# Fri3D_2018_LEDS_00.net
KiCad netlist of a schematic drawn in Altium Designer
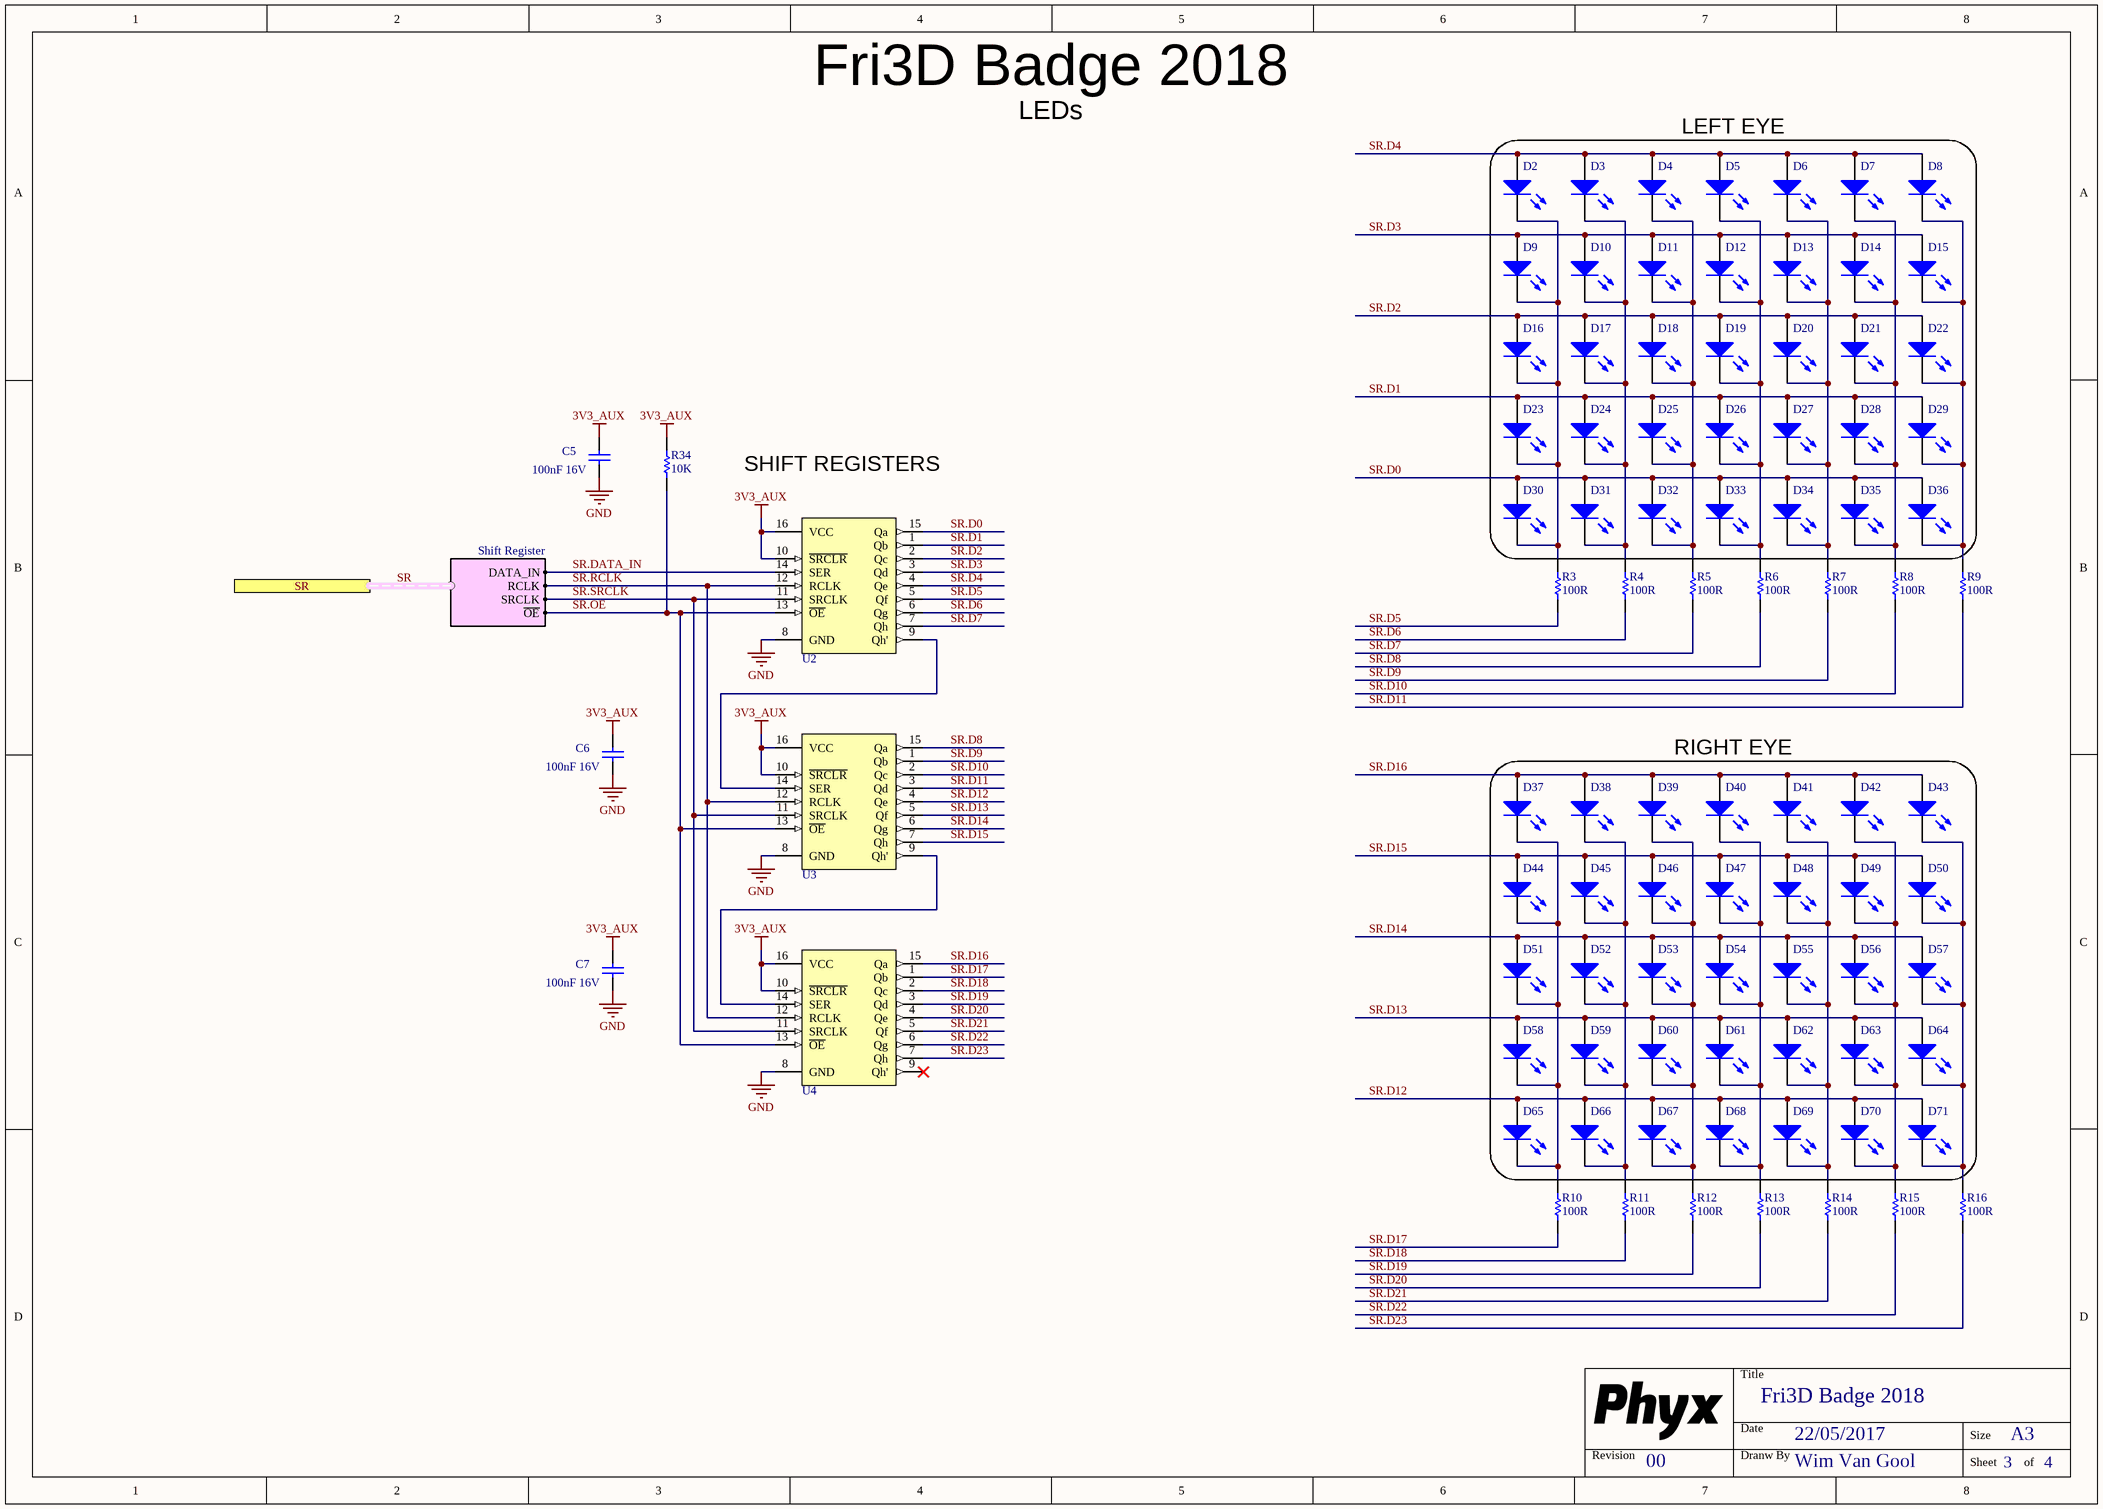
[diagram p0: Fri3D_2018_LEDS_00.SchDoc]

(export (version "E")
  (design (tool "Eeschema 10.0.6"))
  (components
    (comp (ref "C5")
      (value "100nF 16V")
      (footprint "C0603_N")
      (description "Capacitor Ceramic")
      (libsource (lib "Phyx_Components") (part "CAP_CERAMIC"))
    )
    (comp (ref "C6")
      (value "100nF 16V")
      (footprint "C0603_N")
      (description "Capacitor Ceramic")
      (libsource (lib "Phyx_Components") (part "CAP_CERAMIC"))
    )
    (comp (ref "C7")
      (value "100nF 16V")
      (footprint "C0603_N")
      (description "Capacitor Ceramic")
      (libsource (lib "Phyx_Components") (part "CAP_CERAMIC"))
    )
    (comp (ref "D2")
      (value "Default 0805 Blue LED")
      (footprint "LED_0805_BL")
      (description "=Description")
      (libsource (lib "Phyx_Components") (part "LED_BLUE"))
    )
    (comp (ref "D3")
      (value "Default 0805 Blue LED")
      (footprint "LED_0805_BL")
      (description "=Description")
      (libsource (lib "Phyx_Components") (part "LED_BLUE"))
    )
    (comp (ref "D4")
      (value "Default 0805 Blue LED")
      (footprint "LED_0805_BL")
      (description "=Description")
      (libsource (lib "Phyx_Components") (part "LED_BLUE"))
    )
    (comp (ref "D5")
      (value "Default 0805 Blue LED")
      (footprint "LED_0805_BL")
      (description "=Description")
      (libsource (lib "Phyx_Components") (part "LED_BLUE"))
    )
    (comp (ref "D6")
      (value "Default 0805 Blue LED")
      (footprint "LED_0805_BL")
      (description "=Description")
      (libsource (lib "Phyx_Components") (part "LED_BLUE"))
    )
    (comp (ref "D7")
      (value "Default 0805 Blue LED")
      (footprint "LED_0805_BL")
      (description "=Description")
      (libsource (lib "Phyx_Components") (part "LED_BLUE"))
    )
    (comp (ref "D8")
      (value "Default 0805 Blue LED")
      (footprint "LED_0805_BL")
      (description "=Description")
      (libsource (lib "Phyx_Components") (part "LED_BLUE"))
    )
    (comp (ref "D9")
      (value "Default 0805 Blue LED")
      (footprint "LED_0805_BL")
      (description "=Description")
      (libsource (lib "Phyx_Components") (part "LED_BLUE"))
    )
    (comp (ref "D10")
      (value "Default 0805 Blue LED")
      (footprint "LED_0805_BL")
      (description "=Description")
      (libsource (lib "Phyx_Components") (part "LED_BLUE"))
    )
    (comp (ref "D11")
      (value "Default 0805 Blue LED")
      (footprint "LED_0805_BL")
      (description "=Description")
      (libsource (lib "Phyx_Components") (part "LED_BLUE"))
    )
    (comp (ref "D12")
      (value "Default 0805 Blue LED")
      (footprint "LED_0805_BL")
      (description "=Description")
      (libsource (lib "Phyx_Components") (part "LED_BLUE"))
    )
    (comp (ref "D13")
      (value "Default 0805 Blue LED")
      (footprint "LED_0805_BL")
      (description "=Description")
      (libsource (lib "Phyx_Components") (part "LED_BLUE"))
    )
    (comp (ref "D14")
      (value "Default 0805 Blue LED")
      (footprint "LED_0805_BL")
      (description "=Description")
      (libsource (lib "Phyx_Components") (part "LED_BLUE"))
    )
    (comp (ref "D15")
      (value "Default 0805 Blue LED")
      (footprint "LED_0805_BL")
      (description "=Description")
      (libsource (lib "Phyx_Components") (part "LED_BLUE"))
    )
    (comp (ref "D16")
      (value "Default 0805 Blue LED")
      (footprint "LED_0805_BL")
      (description "=Description")
      (libsource (lib "Phyx_Components") (part "LED_BLUE"))
    )
    (comp (ref "D17")
      (value "Default 0805 Blue LED")
      (footprint "LED_0805_BL")
      (description "=Description")
      (libsource (lib "Phyx_Components") (part "LED_BLUE"))
    )
    (comp (ref "D18")
      (value "Default 0805 Blue LED")
      (footprint "LED_0805_BL")
      (description "=Description")
      (libsource (lib "Phyx_Components") (part "LED_BLUE"))
    )
    (comp (ref "D19")
      (value "Default 0805 Blue LED")
      (footprint "LED_0805_BL")
      (description "=Description")
      (libsource (lib "Phyx_Components") (part "LED_BLUE"))
    )
    (comp (ref "D20")
      (value "Default 0805 Blue LED")
      (footprint "LED_0805_BL")
      (description "=Description")
      (libsource (lib "Phyx_Components") (part "LED_BLUE"))
    )
    (comp (ref "D21")
      (value "Default 0805 Blue LED")
      (footprint "LED_0805_BL")
      (description "=Description")
      (libsource (lib "Phyx_Components") (part "LED_BLUE"))
    )
    (comp (ref "D22")
      (value "Default 0805 Blue LED")
      (footprint "LED_0805_BL")
      (description "=Description")
      (libsource (lib "Phyx_Components") (part "LED_BLUE"))
    )
    (comp (ref "D23")
      (value "Default 0805 Blue LED")
      (footprint "LED_0805_BL")
      (description "=Description")
      (libsource (lib "Phyx_Components") (part "LED_BLUE"))
    )
    (comp (ref "D24")
      (value "Default 0805 Blue LED")
      (footprint "LED_0805_BL")
      (description "=Description")
      (libsource (lib "Phyx_Components") (part "LED_BLUE"))
    )
    (comp (ref "D25")
      (value "Default 0805 Blue LED")
      (footprint "LED_0805_BL")
      (description "=Description")
      (libsource (lib "Phyx_Components") (part "LED_BLUE"))
    )
    (comp (ref "D26")
      (value "Default 0805 Blue LED")
      (footprint "LED_0805_BL")
      (description "=Description")
      (libsource (lib "Phyx_Components") (part "LED_BLUE"))
    )
    (comp (ref "D27")
      (value "Default 0805 Blue LED")
      (footprint "LED_0805_BL")
      (description "=Description")
      (libsource (lib "Phyx_Components") (part "LED_BLUE"))
    )
    (comp (ref "D28")
      (value "Default 0805 Blue LED")
      (footprint "LED_0805_BL")
      (description "=Description")
      (libsource (lib "Phyx_Components") (part "LED_BLUE"))
    )
    (comp (ref "D29")
      (value "Default 0805 Blue LED")
      (footprint "LED_0805_BL")
      (description "=Description")
      (libsource (lib "Phyx_Components") (part "LED_BLUE"))
    )
    (comp (ref "D30")
      (value "Default 0805 Blue LED")
      (footprint "LED_0805_BL")
      (description "=Description")
      (libsource (lib "Phyx_Components") (part "LED_BLUE"))
    )
    (comp (ref "D31")
      (value "Default 0805 Blue LED")
      (footprint "LED_0805_BL")
      (description "=Description")
      (libsource (lib "Phyx_Components") (part "LED_BLUE"))
    )
    (comp (ref "D32")
      (value "Default 0805 Blue LED")
      (footprint "LED_0805_BL")
      (description "=Description")
      (libsource (lib "Phyx_Components") (part "LED_BLUE"))
    )
    (comp (ref "D33")
      (value "Default 0805 Blue LED")
      (footprint "LED_0805_BL")
      (description "=Description")
      (libsource (lib "Phyx_Components") (part "LED_BLUE"))
    )
    (comp (ref "D34")
      (value "Default 0805 Blue LED")
      (footprint "LED_0805_BL")
      (description "=Description")
      (libsource (lib "Phyx_Components") (part "LED_BLUE"))
    )
    (comp (ref "D35")
      (value "Default 0805 Blue LED")
      (footprint "LED_0805_BL")
      (description "=Description")
      (libsource (lib "Phyx_Components") (part "LED_BLUE"))
    )
    (comp (ref "D36")
      (value "Default 0805 Blue LED")
      (footprint "LED_0805_BL")
      (description "=Description")
      (libsource (lib "Phyx_Components") (part "LED_BLUE"))
    )
    (comp (ref "D37")
      (value "Default 0805 Blue LED")
      (footprint "LED_0805_BL")
      (description "=Description")
      (libsource (lib "Phyx_Components") (part "LED_BLUE"))
    )
    (comp (ref "D38")
      (value "Default 0805 Blue LED")
      (footprint "LED_0805_BL")
      (description "=Description")
      (libsource (lib "Phyx_Components") (part "LED_BLUE"))
    )
    (comp (ref "D39")
      (value "Default 0805 Blue LED")
      (footprint "LED_0805_BL")
      (description "=Description")
      (libsource (lib "Phyx_Components") (part "LED_BLUE"))
    )
    (comp (ref "D40")
      (value "Default 0805 Blue LED")
      (footprint "LED_0805_BL")
      (description "=Description")
      (libsource (lib "Phyx_Components") (part "LED_BLUE"))
    )
    (comp (ref "D41")
      (value "Default 0805 Blue LED")
      (footprint "LED_0805_BL")
      (description "=Description")
      (libsource (lib "Phyx_Components") (part "LED_BLUE"))
    )
    (comp (ref "D42")
      (value "Default 0805 Blue LED")
      (footprint "LED_0805_BL")
      (description "=Description")
      (libsource (lib "Phyx_Components") (part "LED_BLUE"))
    )
    (comp (ref "D43")
      (value "Default 0805 Blue LED")
      (footprint "LED_0805_BL")
      (description "=Description")
      (libsource (lib "Phyx_Components") (part "LED_BLUE"))
    )
    (comp (ref "D44")
      (value "Default 0805 Blue LED")
      (footprint "LED_0805_BL")
      (description "=Description")
      (libsource (lib "Phyx_Components") (part "LED_BLUE"))
    )
    (comp (ref "D45")
      (value "Default 0805 Blue LED")
      (footprint "LED_0805_BL")
      (description "=Description")
      (libsource (lib "Phyx_Components") (part "LED_BLUE"))
    )
    (comp (ref "D46")
      (value "Default 0805 Blue LED")
      (footprint "LED_0805_BL")
      (description "=Description")
      (libsource (lib "Phyx_Components") (part "LED_BLUE"))
    )
    (comp (ref "D47")
      (value "Default 0805 Blue LED")
      (footprint "LED_0805_BL")
      (description "=Description")
      (libsource (lib "Phyx_Components") (part "LED_BLUE"))
    )
    (comp (ref "D48")
      (value "Default 0805 Blue LED")
      (footprint "LED_0805_BL")
      (description "=Description")
      (libsource (lib "Phyx_Components") (part "LED_BLUE"))
    )
    (comp (ref "D49")
      (value "Default 0805 Blue LED")
      (footprint "LED_0805_BL")
      (description "=Description")
      (libsource (lib "Phyx_Components") (part "LED_BLUE"))
    )
    (comp (ref "D50")
      (value "Default 0805 Blue LED")
      (footprint "LED_0805_BL")
      (description "=Description")
      (libsource (lib "Phyx_Components") (part "LED_BLUE"))
    )
    (comp (ref "D51")
      (value "Default 0805 Blue LED")
      (footprint "LED_0805_BL")
      (description "=Description")
      (libsource (lib "Phyx_Components") (part "LED_BLUE"))
    )
    (comp (ref "D52")
      (value "Default 0805 Blue LED")
      (footprint "LED_0805_BL")
      (description "=Description")
      (libsource (lib "Phyx_Components") (part "LED_BLUE"))
    )
    (comp (ref "D53")
      (value "Default 0805 Blue LED")
      (footprint "LED_0805_BL")
      (description "=Description")
      (libsource (lib "Phyx_Components") (part "LED_BLUE"))
    )
    (comp (ref "D54")
      (value "Default 0805 Blue LED")
      (footprint "LED_0805_BL")
      (description "=Description")
      (libsource (lib "Phyx_Components") (part "LED_BLUE"))
    )
    (comp (ref "D55")
      (value "Default 0805 Blue LED")
      (footprint "LED_0805_BL")
      (description "=Description")
      (libsource (lib "Phyx_Components") (part "LED_BLUE"))
    )
    (comp (ref "D56")
      (value "Default 0805 Blue LED")
      (footprint "LED_0805_BL")
      (description "=Description")
      (libsource (lib "Phyx_Components") (part "LED_BLUE"))
    )
    (comp (ref "D57")
      (value "Default 0805 Blue LED")
      (footprint "LED_0805_BL")
      (description "=Description")
      (libsource (lib "Phyx_Components") (part "LED_BLUE"))
    )
    (comp (ref "D58")
      (value "Default 0805 Blue LED")
      (footprint "LED_0805_BL")
      (description "=Description")
      (libsource (lib "Phyx_Components") (part "LED_BLUE"))
    )
    (comp (ref "D59")
      (value "Default 0805 Blue LED")
      (footprint "LED_0805_BL")
      (description "=Description")
      (libsource (lib "Phyx_Components") (part "LED_BLUE"))
    )
    (comp (ref "D60")
      (value "Default 0805 Blue LED")
      (footprint "LED_0805_BL")
      (description "=Description")
      (libsource (lib "Phyx_Components") (part "LED_BLUE"))
    )
    (comp (ref "D61")
      (value "Default 0805 Blue LED")
      (footprint "LED_0805_BL")
      (description "=Description")
      (libsource (lib "Phyx_Components") (part "LED_BLUE"))
    )
    (comp (ref "D62")
      (value "Default 0805 Blue LED")
      (footprint "LED_0805_BL")
      (description "=Description")
      (libsource (lib "Phyx_Components") (part "LED_BLUE"))
    )
    (comp (ref "D63")
      (value "Default 0805 Blue LED")
      (footprint "LED_0805_BL")
      (description "=Description")
      (libsource (lib "Phyx_Components") (part "LED_BLUE"))
    )
    (comp (ref "D64")
      (value "Default 0805 Blue LED")
      (footprint "LED_0805_BL")
      (description "=Description")
      (libsource (lib "Phyx_Components") (part "LED_BLUE"))
    )
    (comp (ref "D65")
      (value "Default 0805 Blue LED")
      (footprint "LED_0805_BL")
      (description "=Description")
      (libsource (lib "Phyx_Components") (part "LED_BLUE"))
    )
    (comp (ref "D66")
      (value "Default 0805 Blue LED")
      (footprint "LED_0805_BL")
      (description "=Description")
      (libsource (lib "Phyx_Components") (part "LED_BLUE"))
    )
    (comp (ref "D67")
      (value "Default 0805 Blue LED")
      (footprint "LED_0805_BL")
      (description "=Description")
      (libsource (lib "Phyx_Components") (part "LED_BLUE"))
    )
    (comp (ref "D68")
      (value "Default 0805 Blue LED")
      (footprint "LED_0805_BL")
      (description "=Description")
      (libsource (lib "Phyx_Components") (part "LED_BLUE"))
    )
    (comp (ref "D69")
      (value "Default 0805 Blue LED")
      (footprint "LED_0805_BL")
      (description "=Description")
      (libsource (lib "Phyx_Components") (part "LED_BLUE"))
    )
    (comp (ref "D70")
      (value "Default 0805 Blue LED")
      (footprint "LED_0805_BL")
      (description "=Description")
      (libsource (lib "Phyx_Components") (part "LED_BLUE"))
    )
    (comp (ref "D71")
      (value "Default 0805 Blue LED")
      (footprint "LED_0805_BL")
      (description "=Description")
      (libsource (lib "Phyx_Components") (part "LED_BLUE"))
    )
    (comp (ref "R3")
      (value "100R")
      (footprint "R0603_N")
      (fields (field (name "Comment") "RESISTOR"))
      (libsource (lib "Phyx_Components") (part "RESISTOR"))
    )
    (comp (ref "R4")
      (value "100R")
      (footprint "R0603_N")
      (fields (field (name "Comment") "RESISTOR"))
      (libsource (lib "Phyx_Components") (part "RESISTOR"))
    )
    (comp (ref "R5")
      (value "100R")
      (footprint "R0603_N")
      (fields (field (name "Comment") "RESISTOR"))
      (libsource (lib "Phyx_Components") (part "RESISTOR"))
    )
    (comp (ref "R6")
      (value "100R")
      (footprint "R0603_N")
      (fields (field (name "Comment") "RESISTOR"))
      (libsource (lib "Phyx_Components") (part "RESISTOR"))
    )
    (comp (ref "R7")
      (value "100R")
      (footprint "R0603_N")
      (fields (field (name "Comment") "RESISTOR"))
      (libsource (lib "Phyx_Components") (part "RESISTOR"))
    )
    (comp (ref "R8")
      (value "100R")
      (footprint "R0603_N")
      (fields (field (name "Comment") "RESISTOR"))
      (libsource (lib "Phyx_Components") (part "RESISTOR"))
    )
    (comp (ref "R9")
      (value "100R")
      (footprint "R0603_N")
      (fields (field (name "Comment") "RESISTOR"))
      (libsource (lib "Phyx_Components") (part "RESISTOR"))
    )
    (comp (ref "R10")
      (value "100R")
      (footprint "R0603_N")
      (fields (field (name "Comment") "RESISTOR"))
      (libsource (lib "Phyx_Components") (part "RESISTOR"))
    )
    (comp (ref "R11")
      (value "100R")
      (footprint "R0603_N")
      (fields (field (name "Comment") "RESISTOR"))
      (libsource (lib "Phyx_Components") (part "RESISTOR"))
    )
    (comp (ref "R12")
      (value "100R")
      (footprint "R0603_N")
      (fields (field (name "Comment") "RESISTOR"))
      (libsource (lib "Phyx_Components") (part "RESISTOR"))
    )
    (comp (ref "R13")
      (value "100R")
      (footprint "R0603_N")
      (fields (field (name "Comment") "RESISTOR"))
      (libsource (lib "Phyx_Components") (part "RESISTOR"))
    )
    (comp (ref "R14")
      (value "100R")
      (footprint "R0603_N")
      (fields (field (name "Comment") "RESISTOR"))
      (libsource (lib "Phyx_Components") (part "RESISTOR"))
    )
    (comp (ref "R15")
      (value "100R")
      (footprint "R0603_N")
      (fields (field (name "Comment") "RESISTOR"))
      (libsource (lib "Phyx_Components") (part "RESISTOR"))
    )
    (comp (ref "R16")
      (value "100R")
      (footprint "R0603_N")
      (fields (field (name "Comment") "RESISTOR"))
      (libsource (lib "Phyx_Components") (part "RESISTOR"))
    )
    (comp (ref "R34")
      (value "10K")
      (footprint "R0603_N")
      (fields (field (name "Comment") "RESISTOR"))
      (libsource (lib "Phyx_Components") (part "RESISTOR"))
    )
    (comp (ref "U2")
      (value "8-Bit Shift Registers With 3-State Output Registers")
      (footprint "SOIC_N_16")
      (description "=Description")
      (libsource (lib "Phyx_Components") (part "74HC595"))
    )
    (comp (ref "U3")
      (value "8-Bit Shift Registers With 3-State Output Registers")
      (footprint "SOIC_N_16")
      (description "=Description")
      (libsource (lib "Phyx_Components") (part "74HC595"))
    )
    (comp (ref "U4")
      (value "8-Bit Shift Registers With 3-State Output Registers")
      (footprint "SOIC_N_16")
      (description "=Description")
      (libsource (lib "Phyx_Components") (part "74HC595"))
    )
  )
  (nets
    (net (code "3") (name "/SR.D0") (class "Default")
      (node (ref "D30") (pin "1") (pinfunction "A_1") (pintype "passive"))
      (node (ref "D31") (pin "1") (pinfunction "A_1") (pintype "passive"))
      (node (ref "D32") (pin "1") (pinfunction "A_1") (pintype "passive"))
      (node (ref "D33") (pin "1") (pinfunction "A_1") (pintype "passive"))
      (node (ref "D34") (pin "1") (pinfunction "A_1") (pintype "passive"))
      (node (ref "D35") (pin "1") (pinfunction "A_1") (pintype "passive"))
      (node (ref "D36") (pin "1") (pinfunction "A_1") (pintype "passive"))
      (node (ref "U2") (pin "15") (pinfunction "Qa_15") (pintype "output"))
    )
    (net (code "4") (name "/SR.D1") (class "Default")
      (node (ref "D23") (pin "1") (pinfunction "A_1") (pintype "passive"))
      (node (ref "D24") (pin "1") (pinfunction "A_1") (pintype "passive"))
      (node (ref "D25") (pin "1") (pinfunction "A_1") (pintype "passive"))
      (node (ref "D26") (pin "1") (pinfunction "A_1") (pintype "passive"))
      (node (ref "D27") (pin "1") (pinfunction "A_1") (pintype "passive"))
      (node (ref "D28") (pin "1") (pinfunction "A_1") (pintype "passive"))
      (node (ref "D29") (pin "1") (pinfunction "A_1") (pintype "passive"))
      (node (ref "U2") (pin "1") (pinfunction "Qb_1") (pintype "output"))
    )
    (net (code "5") (name "/SR.D2") (class "Default")
      (node (ref "D16") (pin "1") (pinfunction "A_1") (pintype "passive"))
      (node (ref "D17") (pin "1") (pinfunction "A_1") (pintype "passive"))
      (node (ref "D18") (pin "1") (pinfunction "A_1") (pintype "passive"))
      (node (ref "D19") (pin "1") (pinfunction "A_1") (pintype "passive"))
      (node (ref "D20") (pin "1") (pinfunction "A_1") (pintype "passive"))
      (node (ref "D21") (pin "1") (pinfunction "A_1") (pintype "passive"))
      (node (ref "D22") (pin "1") (pinfunction "A_1") (pintype "passive"))
      (node (ref "U2") (pin "2") (pinfunction "Qc_2") (pintype "output"))
    )
    (net (code "6") (name "/SR.D3") (class "Default")
      (node (ref "D10") (pin "1") (pinfunction "A_1") (pintype "passive"))
      (node (ref "D11") (pin "1") (pinfunction "A_1") (pintype "passive"))
      (node (ref "D12") (pin "1") (pinfunction "A_1") (pintype "passive"))
      (node (ref "D13") (pin "1") (pinfunction "A_1") (pintype "passive"))
      (node (ref "D14") (pin "1") (pinfunction "A_1") (pintype "passive"))
      (node (ref "D15") (pin "1") (pinfunction "A_1") (pintype "passive"))
      (node (ref "D9") (pin "1") (pinfunction "A_1") (pintype "passive"))
      (node (ref "U2") (pin "3") (pinfunction "Qd_3") (pintype "output"))
    )
    (net (code "7") (name "/SR.D4") (class "Default")
      (node (ref "D2") (pin "1") (pinfunction "A_1") (pintype "passive"))
      (node (ref "D3") (pin "1") (pinfunction "A_1") (pintype "passive"))
      (node (ref "D4") (pin "1") (pinfunction "A_1") (pintype "passive"))
      (node (ref "D5") (pin "1") (pinfunction "A_1") (pintype "passive"))
      (node (ref "D6") (pin "1") (pinfunction "A_1") (pintype "passive"))
      (node (ref "D7") (pin "1") (pinfunction "A_1") (pintype "passive"))
      (node (ref "D8") (pin "1") (pinfunction "A_1") (pintype "passive"))
      (node (ref "U2") (pin "4") (pinfunction "Qe_4") (pintype "output"))
    )
    (net (code "8") (name "/SR.D5") (class "Default")
      (node (ref "R3") (pin "2") (pinfunction "2_2") (pintype "passive"))
      (node (ref "U2") (pin "5") (pinfunction "Qf_5") (pintype "output"))
    )
    (net (code "9") (name "/SR.D6") (class "Default")
      (node (ref "R4") (pin "2") (pinfunction "2_2") (pintype "passive"))
      (node (ref "U2") (pin "6") (pinfunction "Qg_6") (pintype "output"))
    )
    (net (code "10") (name "/SR.D7") (class "Default")
      (node (ref "R5") (pin "2") (pinfunction "2_2") (pintype "passive"))
      (node (ref "U2") (pin "7") (pinfunction "Qh_7") (pintype "output"))
    )
    (net (code "11") (name "/SR.D8") (class "Default")
      (node (ref "R6") (pin "2") (pinfunction "2_2") (pintype "passive"))
      (node (ref "U3") (pin "15") (pinfunction "Qa_15") (pintype "output"))
    )
    (net (code "12") (name "/SR.D9") (class "Default")
      (node (ref "R7") (pin "2") (pinfunction "2_2") (pintype "passive"))
      (node (ref "U3") (pin "1") (pinfunction "Qb_1") (pintype "output"))
    )
    (net (code "13") (name "/SR.D10") (class "Default")
      (node (ref "R8") (pin "2") (pinfunction "2_2") (pintype "passive"))
      (node (ref "U3") (pin "2") (pinfunction "Qc_2") (pintype "output"))
    )
    (net (code "14") (name "/SR.D11") (class "Default")
      (node (ref "R9") (pin "2") (pinfunction "2_2") (pintype "passive"))
      (node (ref "U3") (pin "3") (pinfunction "Qd_3") (pintype "output"))
    )
    (net (code "15") (name "/SR.D12") (class "Default")
      (node (ref "D65") (pin "1") (pinfunction "A_1") (pintype "passive"))
      (node (ref "D66") (pin "1") (pinfunction "A_1") (pintype "passive"))
      (node (ref "D67") (pin "1") (pinfunction "A_1") (pintype "passive"))
      (node (ref "D68") (pin "1") (pinfunction "A_1") (pintype "passive"))
      (node (ref "D69") (pin "1") (pinfunction "A_1") (pintype "passive"))
      (node (ref "D70") (pin "1") (pinfunction "A_1") (pintype "passive"))
      (node (ref "D71") (pin "1") (pinfunction "A_1") (pintype "passive"))
      (node (ref "U3") (pin "4") (pinfunction "Qe_4") (pintype "output"))
    )
    (net (code "16") (name "/SR.D13") (class "Default")
      (node (ref "D58") (pin "1") (pinfunction "A_1") (pintype "passive"))
      (node (ref "D59") (pin "1") (pinfunction "A_1") (pintype "passive"))
      (node (ref "D60") (pin "1") (pinfunction "A_1") (pintype "passive"))
      (node (ref "D61") (pin "1") (pinfunction "A_1") (pintype "passive"))
      (node (ref "D62") (pin "1") (pinfunction "A_1") (pintype "passive"))
      (node (ref "D63") (pin "1") (pinfunction "A_1") (pintype "passive"))
      (node (ref "D64") (pin "1") (pinfunction "A_1") (pintype "passive"))
      (node (ref "U3") (pin "5") (pinfunction "Qf_5") (pintype "output"))
    )
    (net (code "17") (name "/SR.D14") (class "Default")
      (node (ref "D51") (pin "1") (pinfunction "A_1") (pintype "passive"))
      (node (ref "D52") (pin "1") (pinfunction "A_1") (pintype "passive"))
      (node (ref "D53") (pin "1") (pinfunction "A_1") (pintype "passive"))
      (node (ref "D54") (pin "1") (pinfunction "A_1") (pintype "passive"))
      (node (ref "D55") (pin "1") (pinfunction "A_1") (pintype "passive"))
      (node (ref "D56") (pin "1") (pinfunction "A_1") (pintype "passive"))
      (node (ref "D57") (pin "1") (pinfunction "A_1") (pintype "passive"))
      (node (ref "U3") (pin "6") (pinfunction "Qg_6") (pintype "output"))
    )
    (net (code "18") (name "/SR.D15") (class "Default")
      (node (ref "D44") (pin "1") (pinfunction "A_1") (pintype "passive"))
      (node (ref "D45") (pin "1") (pinfunction "A_1") (pintype "passive"))
      (node (ref "D46") (pin "1") (pinfunction "A_1") (pintype "passive"))
      (node (ref "D47") (pin "1") (pinfunction "A_1") (pintype "passive"))
      (node (ref "D48") (pin "1") (pinfunction "A_1") (pintype "passive"))
      (node (ref "D49") (pin "1") (pinfunction "A_1") (pintype "passive"))
      (node (ref "D50") (pin "1") (pinfunction "A_1") (pintype "passive"))
      (node (ref "U3") (pin "7") (pinfunction "Qh_7") (pintype "output"))
    )
    (net (code "19") (name "/SR.D16") (class "Default")
      (node (ref "D37") (pin "1") (pinfunction "A_1") (pintype "passive"))
      (node (ref "D38") (pin "1") (pinfunction "A_1") (pintype "passive"))
      (node (ref "D39") (pin "1") (pinfunction "A_1") (pintype "passive"))
      (node (ref "D40") (pin "1") (pinfunction "A_1") (pintype "passive"))
      (node (ref "D41") (pin "1") (pinfunction "A_1") (pintype "passive"))
      (node (ref "D42") (pin "1") (pinfunction "A_1") (pintype "passive"))
      (node (ref "D43") (pin "1") (pinfunction "A_1") (pintype "passive"))
      (node (ref "U4") (pin "15") (pinfunction "Qa_15") (pintype "output"))
    )
    (net (code "20") (name "/SR.D17") (class "Default")
      (node (ref "R10") (pin "2") (pinfunction "2_2") (pintype "passive"))
      (node (ref "U4") (pin "1") (pinfunction "Qb_1") (pintype "output"))
    )
    (net (code "21") (name "/SR.D18") (class "Default")
      (node (ref "R11") (pin "2") (pinfunction "2_2") (pintype "passive"))
      (node (ref "U4") (pin "2") (pinfunction "Qc_2") (pintype "output"))
    )
    (net (code "22") (name "/SR.D19") (class "Default")
      (node (ref "R12") (pin "2") (pinfunction "2_2") (pintype "passive"))
      (node (ref "U4") (pin "3") (pinfunction "Qd_3") (pintype "output"))
    )
    (net (code "23") (name "/SR.D20") (class "Default")
      (node (ref "R13") (pin "2") (pinfunction "2_2") (pintype "passive"))
      (node (ref "U4") (pin "4") (pinfunction "Qe_4") (pintype "output"))
    )
    (net (code "24") (name "/SR.D21") (class "Default")
      (node (ref "R14") (pin "2") (pinfunction "2_2") (pintype "passive"))
      (node (ref "U4") (pin "5") (pinfunction "Qf_5") (pintype "output"))
    )
    (net (code "25") (name "/SR.D22") (class "Default")
      (node (ref "R15") (pin "2") (pinfunction "2_2") (pintype "passive"))
      (node (ref "U4") (pin "6") (pinfunction "Qg_6") (pintype "output"))
    )
    (net (code "26") (name "/SR.D23") (class "Default")
      (node (ref "R16") (pin "2") (pinfunction "2_2") (pintype "passive"))
      (node (ref "U4") (pin "7") (pinfunction "Qh_7") (pintype "output"))
    )
    (net (code "27") (name "/SR.DATA_IN") (class "Default")
      (node (ref "U2") (pin "14") (pinfunction "SER_14") (pintype "input"))
    )
    (net (code "28") (name "/SR.RCLK") (class "Default")
      (node (ref "U2") (pin "12") (pinfunction "RCLK_12") (pintype "input"))
      (node (ref "U3") (pin "12") (pinfunction "RCLK_12") (pintype "input"))
      (node (ref "U4") (pin "12") (pinfunction "RCLK_12") (pintype "input"))
    )
    (net (code "29") (name "/SR.SRCLK") (class "Default")
      (node (ref "U2") (pin "11") (pinfunction "SRCLK_11") (pintype "input"))
      (node (ref "U3") (pin "11") (pinfunction "SRCLK_11") (pintype "input"))
      (node (ref "U4") (pin "11") (pinfunction "SRCLK_11") (pintype "input"))
    )
    (net (code "30") (name "/SR.~{OE}") (class "Default")
      (node (ref "R34") (pin "2") (pinfunction "2_2") (pintype "passive"))
      (node (ref "U2") (pin "13") (pinfunction "~{OE}_13") (pintype "input"))
      (node (ref "U3") (pin "13") (pinfunction "~{OE}_13") (pintype "input"))
      (node (ref "U4") (pin "13") (pinfunction "~{OE}_13") (pintype "input"))
    )
    (net (code "32") (name "3V3_AUX") (class "Default")
      (node (ref "C5") (pin "1") (pinfunction "1_1") (pintype "passive"))
      (node (ref "C6") (pin "1") (pinfunction "1_1") (pintype "passive"))
      (node (ref "C7") (pin "1") (pinfunction "1_1") (pintype "passive"))
      (node (ref "R34") (pin "1") (pinfunction "1_1") (pintype "passive"))
      (node (ref "U2") (pin "10") (pinfunction "~{SRCLR}_10") (pintype "input"))
      (node (ref "U2") (pin "16") (pinfunction "VCC_16") (pintype "power_in"))
      (node (ref "U3") (pin "10") (pinfunction "~{SRCLR}_10") (pintype "input"))
      (node (ref "U3") (pin "16") (pinfunction "VCC_16") (pintype "power_in"))
      (node (ref "U4") (pin "10") (pinfunction "~{SRCLR}_10") (pintype "input"))
      (node (ref "U4") (pin "16") (pinfunction "VCC_16") (pintype "power_in"))
    )
    (net (code "33") (name "GND") (class "Default")
      (node (ref "C5") (pin "2") (pinfunction "2_2") (pintype "passive"))
      (node (ref "C6") (pin "2") (pinfunction "2_2") (pintype "passive"))
      (node (ref "C7") (pin "2") (pinfunction "2_2") (pintype "passive"))
      (node (ref "U2") (pin "8") (pinfunction "GND_8") (pintype "power_in"))
      (node (ref "U3") (pin "8") (pinfunction "GND_8") (pintype "power_in"))
      (node (ref "U4") (pin "8") (pinfunction "GND_8") (pintype "power_in"))
    )
    (net (code "34") (name "Net-(D10-K)") (class "Default")
      (node (ref "D10") (pin "2") (pinfunction "K_2") (pintype "passive"))
      (node (ref "D17") (pin "2") (pinfunction "K_2") (pintype "passive"))
      (node (ref "D24") (pin "2") (pinfunction "K_2") (pintype "passive"))
      (node (ref "D3") (pin "2") (pinfunction "K_2") (pintype "passive"))
      (node (ref "D31") (pin "2") (pinfunction "K_2") (pintype "passive"))
      (node (ref "R4") (pin "1") (pinfunction "1_1") (pintype "passive"))
    )
    (net (code "35") (name "Net-(D11-K)") (class "Default")
      (node (ref "D11") (pin "2") (pinfunction "K_2") (pintype "passive"))
      (node (ref "D18") (pin "2") (pinfunction "K_2") (pintype "passive"))
      (node (ref "D25") (pin "2") (pinfunction "K_2") (pintype "passive"))
      (node (ref "D32") (pin "2") (pinfunction "K_2") (pintype "passive"))
      (node (ref "D4") (pin "2") (pinfunction "K_2") (pintype "passive"))
      (node (ref "R5") (pin "1") (pinfunction "1_1") (pintype "passive"))
    )
    (net (code "36") (name "Net-(D12-K)") (class "Default")
      (node (ref "D12") (pin "2") (pinfunction "K_2") (pintype "passive"))
      (node (ref "D19") (pin "2") (pinfunction "K_2") (pintype "passive"))
      (node (ref "D26") (pin "2") (pinfunction "K_2") (pintype "passive"))
      (node (ref "D33") (pin "2") (pinfunction "K_2") (pintype "passive"))
      (node (ref "D5") (pin "2") (pinfunction "K_2") (pintype "passive"))
      (node (ref "R6") (pin "1") (pinfunction "1_1") (pintype "passive"))
    )
    (net (code "37") (name "Net-(D13-K)") (class "Default")
      (node (ref "D13") (pin "2") (pinfunction "K_2") (pintype "passive"))
      (node (ref "D20") (pin "2") (pinfunction "K_2") (pintype "passive"))
      (node (ref "D27") (pin "2") (pinfunction "K_2") (pintype "passive"))
      (node (ref "D34") (pin "2") (pinfunction "K_2") (pintype "passive"))
      (node (ref "D6") (pin "2") (pinfunction "K_2") (pintype "passive"))
      (node (ref "R7") (pin "1") (pinfunction "1_1") (pintype "passive"))
    )
    (net (code "38") (name "Net-(D14-K)") (class "Default")
      (node (ref "D14") (pin "2") (pinfunction "K_2") (pintype "passive"))
      (node (ref "D21") (pin "2") (pinfunction "K_2") (pintype "passive"))
      (node (ref "D28") (pin "2") (pinfunction "K_2") (pintype "passive"))
      (node (ref "D35") (pin "2") (pinfunction "K_2") (pintype "passive"))
      (node (ref "D7") (pin "2") (pinfunction "K_2") (pintype "passive"))
      (node (ref "R8") (pin "1") (pinfunction "1_1") (pintype "passive"))
    )
    (net (code "39") (name "Net-(D15-K)") (class "Default")
      (node (ref "D15") (pin "2") (pinfunction "K_2") (pintype "passive"))
      (node (ref "D22") (pin "2") (pinfunction "K_2") (pintype "passive"))
      (node (ref "D29") (pin "2") (pinfunction "K_2") (pintype "passive"))
      (node (ref "D36") (pin "2") (pinfunction "K_2") (pintype "passive"))
      (node (ref "D8") (pin "2") (pinfunction "K_2") (pintype "passive"))
      (node (ref "R9") (pin "1") (pinfunction "1_1") (pintype "passive"))
    )
    (net (code "40") (name "Net-(D16-K)") (class "Default")
      (node (ref "D16") (pin "2") (pinfunction "K_2") (pintype "passive"))
      (node (ref "D2") (pin "2") (pinfunction "K_2") (pintype "passive"))
      (node (ref "D23") (pin "2") (pinfunction "K_2") (pintype "passive"))
      (node (ref "D30") (pin "2") (pinfunction "K_2") (pintype "passive"))
      (node (ref "D9") (pin "2") (pinfunction "K_2") (pintype "passive"))
      (node (ref "R3") (pin "1") (pinfunction "1_1") (pintype "passive"))
    )
    (net (code "41") (name "Net-(D37-K)") (class "Default")
      (node (ref "D37") (pin "2") (pinfunction "K_2") (pintype "passive"))
      (node (ref "D44") (pin "2") (pinfunction "K_2") (pintype "passive"))
      (node (ref "D51") (pin "2") (pinfunction "K_2") (pintype "passive"))
      (node (ref "D58") (pin "2") (pinfunction "K_2") (pintype "passive"))
      (node (ref "D65") (pin "2") (pinfunction "K_2") (pintype "passive"))
      (node (ref "R10") (pin "1") (pinfunction "1_1") (pintype "passive"))
    )
    (net (code "42") (name "Net-(D38-K)") (class "Default")
      (node (ref "D38") (pin "2") (pinfunction "K_2") (pintype "passive"))
      (node (ref "D45") (pin "2") (pinfunction "K_2") (pintype "passive"))
      (node (ref "D52") (pin "2") (pinfunction "K_2") (pintype "passive"))
      (node (ref "D59") (pin "2") (pinfunction "K_2") (pintype "passive"))
      (node (ref "D66") (pin "2") (pinfunction "K_2") (pintype "passive"))
      (node (ref "R11") (pin "1") (pinfunction "1_1") (pintype "passive"))
    )
    (net (code "43") (name "Net-(D39-K)") (class "Default")
      (node (ref "D39") (pin "2") (pinfunction "K_2") (pintype "passive"))
      (node (ref "D46") (pin "2") (pinfunction "K_2") (pintype "passive"))
      (node (ref "D53") (pin "2") (pinfunction "K_2") (pintype "passive"))
      (node (ref "D60") (pin "2") (pinfunction "K_2") (pintype "passive"))
      (node (ref "D67") (pin "2") (pinfunction "K_2") (pintype "passive"))
      (node (ref "R12") (pin "1") (pinfunction "1_1") (pintype "passive"))
    )
    (net (code "44") (name "Net-(D40-K)") (class "Default")
      (node (ref "D40") (pin "2") (pinfunction "K_2") (pintype "passive"))
      (node (ref "D47") (pin "2") (pinfunction "K_2") (pintype "passive"))
      (node (ref "D54") (pin "2") (pinfunction "K_2") (pintype "passive"))
      (node (ref "D61") (pin "2") (pinfunction "K_2") (pintype "passive"))
      (node (ref "D68") (pin "2") (pinfunction "K_2") (pintype "passive"))
      (node (ref "R13") (pin "1") (pinfunction "1_1") (pintype "passive"))
    )
    (net (code "45") (name "Net-(D41-K)") (class "Default")
      (node (ref "D41") (pin "2") (pinfunction "K_2") (pintype "passive"))
      (node (ref "D48") (pin "2") (pinfunction "K_2") (pintype "passive"))
      (node (ref "D55") (pin "2") (pinfunction "K_2") (pintype "passive"))
      (node (ref "D62") (pin "2") (pinfunction "K_2") (pintype "passive"))
      (node (ref "D69") (pin "2") (pinfunction "K_2") (pintype "passive"))
      (node (ref "R14") (pin "1") (pinfunction "1_1") (pintype "passive"))
    )
    (net (code "46") (name "Net-(D42-K)") (class "Default")
      (node (ref "D42") (pin "2") (pinfunction "K_2") (pintype "passive"))
      (node (ref "D49") (pin "2") (pinfunction "K_2") (pintype "passive"))
      (node (ref "D56") (pin "2") (pinfunction "K_2") (pintype "passive"))
      (node (ref "D63") (pin "2") (pinfunction "K_2") (pintype "passive"))
      (node (ref "D70") (pin "2") (pinfunction "K_2") (pintype "passive"))
      (node (ref "R15") (pin "1") (pinfunction "1_1") (pintype "passive"))
    )
    (net (code "47") (name "Net-(D43-K)") (class "Default")
      (node (ref "D43") (pin "2") (pinfunction "K_2") (pintype "passive"))
      (node (ref "D50") (pin "2") (pinfunction "K_2") (pintype "passive"))
      (node (ref "D57") (pin "2") (pinfunction "K_2") (pintype "passive"))
      (node (ref "D64") (pin "2") (pinfunction "K_2") (pintype "passive"))
      (node (ref "D71") (pin "2") (pinfunction "K_2") (pintype "passive"))
      (node (ref "R16") (pin "1") (pinfunction "1_1") (pintype "passive"))
    )
    (net (code "48") (name "Net-(U2-Qh')") (class "Default")
      (node (ref "U2") (pin "9") (pinfunction "Qh'_9") (pintype "output"))
      (node (ref "U3") (pin "14") (pinfunction "SER_14") (pintype "input"))
    )
    (net (code "49") (name "Net-(U3-Qh')") (class "Default")
      (node (ref "U3") (pin "9") (pinfunction "Qh'_9") (pintype "output"))
      (node (ref "U4") (pin "14") (pinfunction "SER_14") (pintype "input"))
    )
    (net (code "50") (name "unconnected-(U4-Qh'-Pad9)") (class "Default")
      (node (ref "U4") (pin "9") (pinfunction "Qh'_9") (pintype "output+no_connect"))
    )
  )
)
